# Controller-Power.net
KiCad netlist of a schematic drawn in EAGLE
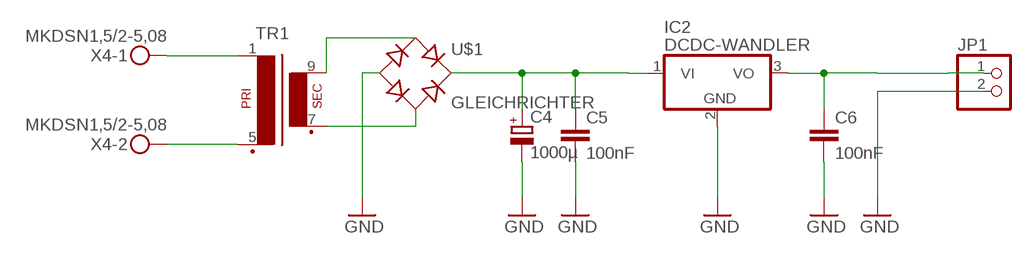
[diagram p0: schematic, sheet 1]

(export (version "E")
  (design (tool "Eeschema 10.0.6"))
  (components
    (comp (ref "C4")
      (value "1000µ")
      (footprint "eagle-import:E3,5-8")
      (libsource (lib "eagle-import") (part "CPOL-EUE3.5-8"))
    )
    (comp (ref "C5")
      (value "100nF")
      (footprint "eagle-import:C0805")
      (libsource (lib "eagle-import") (part "C-EUC0805"))
    )
    (comp (ref "C6")
      (value "100nF")
      (footprint "eagle-import:C0805")
      (libsource (lib "eagle-import") (part "C-EUC0805"))
    )
    (comp (ref "IC2")
      (value "DCDC-WANDLER")
      (footprint "eagle-import:TRACOPOWER-DCDCWANDER-TSR1")
      (libsource (lib "eagle-import") (part "DCDC-WANDLER"))
    )
    (comp (ref "JP1")
      (value "PINHD-1X2")
      (footprint "eagle-import:1X02")
      (libsource (lib "eagle-import") (part "PINHD-1X2"))
    )
    (comp (ref "TR1")
      (value "EI38-1")
      (footprint "eagle-import:EI38-1")
      (libsource (lib "eagle-import") (part "EI38-1"))
    )
    (comp (ref "U$1")
      (value "GLEICHRICHTER")
      (footprint "eagle-import:KBPC1")
      (libsource (lib "eagle-import") (part "GLEICHRICHTER"))
    )
    (comp (ref "X4")
      (value "MKDSN1,5/2-5,08")
      (footprint "eagle-import:MKDSN1,5_2-5,08")
      (libsource (lib "eagle-import") (part "MKDSN1,5/2-5,08"))
    )
  )
  (nets
    (net (code "1") (name "GND") (class "Default")
      (node (ref "C4") (pin "-") (pinfunction "-_-") (pintype "passive"))
      (node (ref "C5") (pin "2") (pinfunction "2_2") (pintype "passive"))
      (node (ref "C6") (pin "2") (pinfunction "2_2") (pintype "passive"))
      (node (ref "IC2") (pin "2") (pinfunction "GND_2") (pintype "passive"))
      (node (ref "JP1") (pin "2") (pinfunction "2_2") (pintype "passive"))
      (node (ref "U$1") (pin "-") (pinfunction "-_-") (pintype "passive"))
    )
    (net (code "2") (name "Net-(IC2-VI)") (class "Default")
      (node (ref "C4") (pin "+") (pinfunction "+_+") (pintype "passive"))
      (node (ref "C5") (pin "1") (pinfunction "1_1") (pintype "passive"))
      (node (ref "IC2") (pin "1") (pinfunction "VI_1") (pintype "input"))
      (node (ref "U$1") (pin "+") (pinfunction "+_+") (pintype "passive"))
    )
    (net (code "3") (name "Net-(IC2-VO)") (class "Default")
      (node (ref "C6") (pin "1") (pinfunction "1_1") (pintype "passive"))
      (node (ref "IC2") (pin "3") (pinfunction "VO_3") (pintype "passive"))
      (node (ref "JP1") (pin "1") (pinfunction "1_1") (pintype "passive"))
    )
    (net (code "4") (name "Net-(TR1-P1)") (class "Default")
      (node (ref "TR1") (pin "1") (pinfunction "P1_1") (pintype "passive"))
      (node (ref "X4") (pin "1") (pinfunction "KL_1") (pintype "passive"))
    )
    (net (code "5") (name "Net-(TR1-P2)") (class "Default")
      (node (ref "TR1") (pin "5") (pinfunction "P2_5") (pintype "passive"))
      (node (ref "X4") (pin "2") (pinfunction "KL_2") (pintype "passive"))
    )
    (net (code "6") (name "Net-(TR1-S3)") (class "Default")
      (node (ref "TR1") (pin "7") (pinfunction "S3_7") (pintype "passive"))
      (node (ref "U$1") (pin "AC2") (pinfunction "AC2_AC2") (pintype "passive"))
    )
    (net (code "7") (name "Net-(TR1-S4)") (class "Default")
      (node (ref "TR1") (pin "9") (pinfunction "S4_9") (pintype "passive"))
      (node (ref "U$1") (pin "AC1") (pinfunction "AC1_AC1") (pintype "passive"))
    )
  )
)
